# power-supplies-hw.net
KiCad netlist of a schematic drawn in Altium Designer
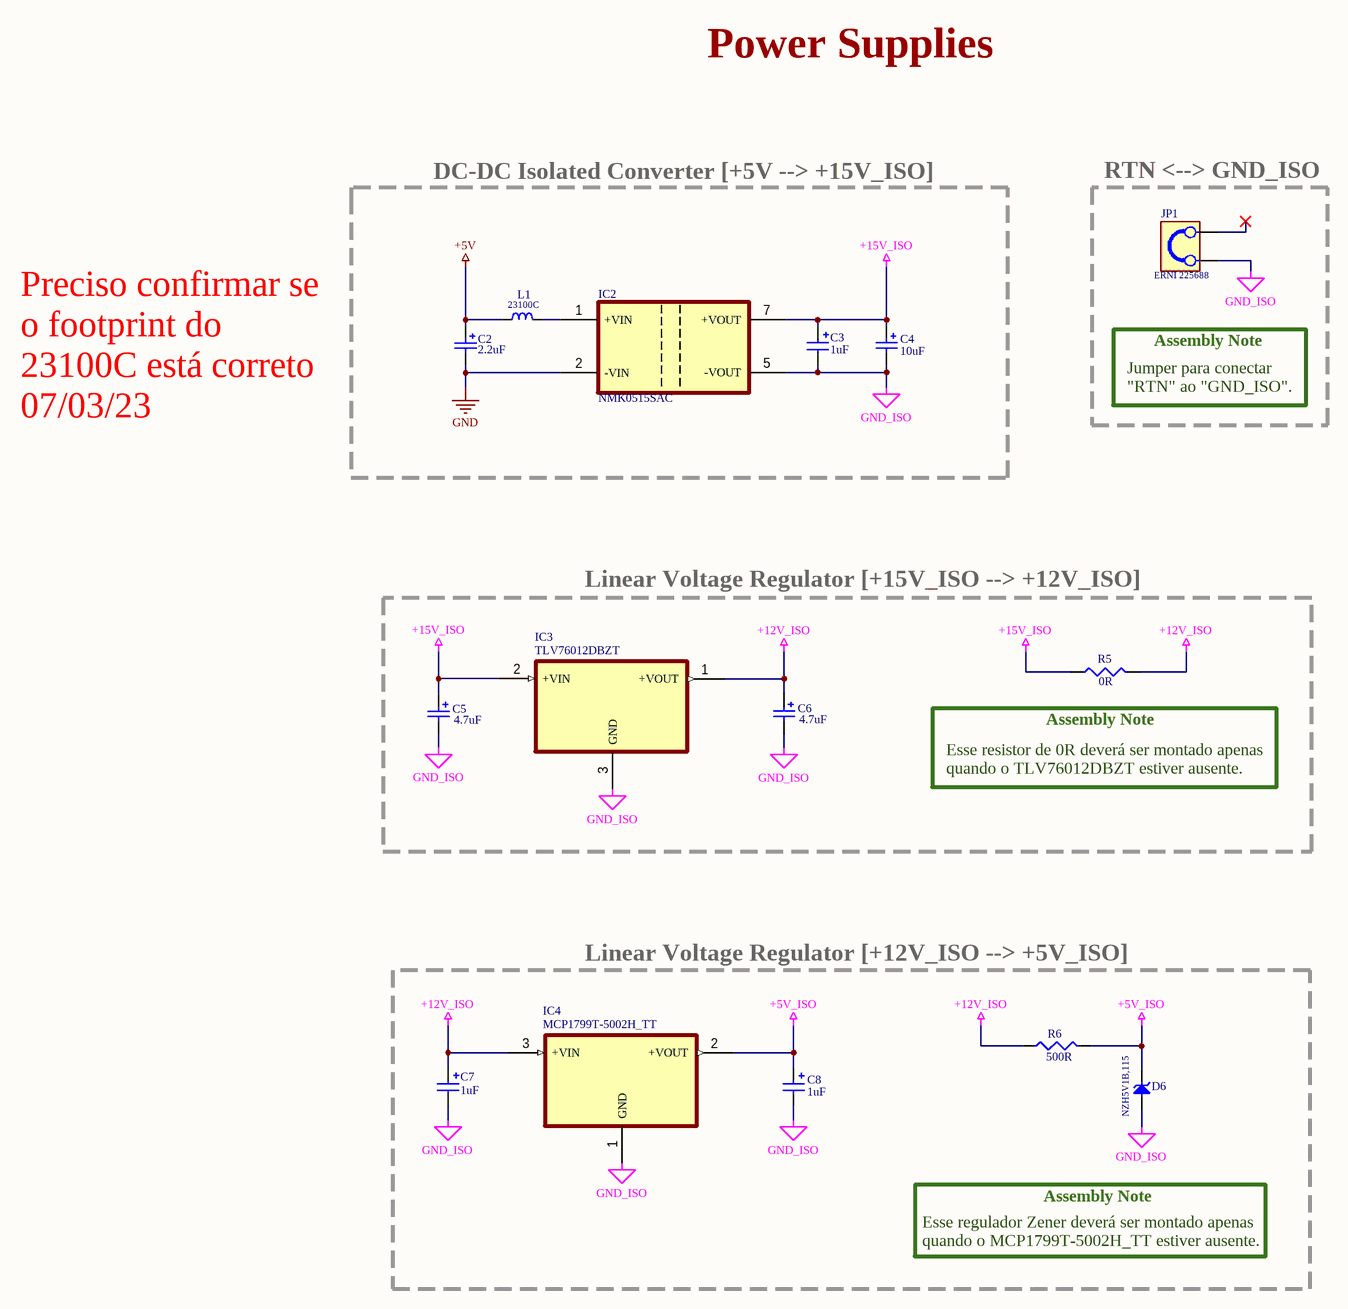
[diagram p0: power-supplies-hw.SchDoc]

(export (version "E")
  (design (tool "Eeschema 10.0.6"))
  (components
    (comp (ref "C2")
      (value "2.2uF")
      (footprint "C1206")
      (libsource (lib "acopians-powerspy-monitoring-hw-library-schematic") (part "Capacitor 2.2uF"))
    )
    (comp (ref "C3")
      (value "1uF")
      (footprint "C1206")
      (libsource (lib "acopians-powerspy-monitoring-hw-library-schematic") (part "Capacitor 1uF"))
    )
    (comp (ref "C4")
      (value "10uF")
      (footprint "C1206")
      (libsource (lib "acopians-powerspy-monitoring-hw-library-schematic") (part "Capacitor 10uF"))
    )
    (comp (ref "C5")
      (value "4.7uF")
      (footprint "C1206")
      (libsource (lib "acopians-powerspy-monitoring-hw-library-schematic") (part "Capacitor 4.7uF"))
    )
    (comp (ref "C6")
      (value "4.7uF")
      (footprint "C1206")
      (libsource (lib "acopians-powerspy-monitoring-hw-library-schematic") (part "Capacitor 4.7uF"))
    )
    (comp (ref "C7")
      (value "1uF")
      (footprint "C1206")
      (libsource (lib "acopians-powerspy-monitoring-hw-library-schematic") (part "Capacitor 1uF"))
    )
    (comp (ref "C8")
      (value "1uF")
      (footprint "C1206")
      (libsource (lib "acopians-powerspy-monitoring-hw-library-schematic") (part "Capacitor 1uF"))
    )
    (comp (ref "D6")
      (value "NZH5V1B,115")
      (footprint "SOD-123F-2")
      (description "5.1V, SOD-123F-2")
      (libsource (lib "acopians-powerspy-monitoring-hw-library-schematic") (part "Zener NZH5V1B,115"))
    )
    (comp (ref "IC2")
      (value "NMK0515SAC")
      (footprint "NMK0515SAC")
      (description "3kVDC Isolated 2W Single Output DC-DC Converter")
      (libsource (lib "acopians-powerspy-monitoring-hw-library-schematic") (part "NMK0515SAC"))
    )
    (comp (ref "IC3")
      (value "TLV76012DBZT")
      (footprint "SOT_23_3")
      (description "Linear-Voltage Regulator, +12V Fixed-Output, 100mA")
      (libsource (lib "acopians-powerspy-monitoring-hw-library-schematic") (part "TLV76012DBZT"))
    )
    (comp (ref "IC4")
      (value "MCP1799T-5002H_TT")
      (footprint "SOT_23_3")
      (description "High-Voltage Automotive LDO, 80mA")
      (libsource (lib "acopians-powerspy-monitoring-hw-library-schematic") (part "MCP1799T-5002H_TT"))
    )
    (comp (ref "JP1")
      (value "ERNI 225688")
      (footprint "ERNI 225688")
      (libsource (lib "acopians-powerspy-monitoring-hw-library-schematic") (part "ERNI 225688"))
    )
    (comp (ref "L1")
      (value "23100C")
      (footprint "23100C")
      (description "Bobbin Wound Surface Mount Inductors, 10uH, 138mOhms, Imax 1.02A")
      (libsource (lib "acopians-powerspy-monitoring-hw-library-schematic") (part "23100C"))
    )
    (comp (ref "R5")
      (value "0R")
      (footprint "R1210")
      (description "Size 1210")
      (libsource (lib "acopians-powerspy-monitoring-hw-library-schematic") (part "Resistor 0R"))
    )
    (comp (ref "R6")
      (value "500R")
      (footprint "Resistor 0805")
      (libsource (lib "acopians-powerspy-monitoring-hw-library-schematic") (part "Resistor 500R"))
    )
  )
  (nets
    (net (code "1") (name "+5V") (class "Default")
      (node (ref "C2") (pin "1") (pinfunction "1_1") (pintype "passive"))
      (node (ref "L1") (pin "1") (pinfunction "1_1") (pintype "passive"))
    )
    (net (code "2") (name "+5V_ISO") (class "Default")
      (node (ref "C8") (pin "1") (pinfunction "1_1") (pintype "passive"))
      (node (ref "D6") (pin "1") (pintype "passive"))
      (node (ref "IC4") (pin "2") (pinfunction "+VOUT_2") (pintype "output"))
      (node (ref "R6") (pin "2") (pinfunction "2_2") (pintype "passive"))
    )
    (net (code "3") (name "+12V_ISO") (class "Default")
      (node (ref "C6") (pin "1") (pinfunction "1_1") (pintype "passive"))
      (node (ref "C7") (pin "1") (pinfunction "1_1") (pintype "passive"))
      (node (ref "IC3") (pin "1") (pinfunction "+VOUT_1") (pintype "output"))
      (node (ref "IC4") (pin "3") (pinfunction "+VIN_3") (pintype "input"))
      (node (ref "R5") (pin "2") (pinfunction "2_2") (pintype "passive"))
      (node (ref "R6") (pin "1") (pinfunction "1_1") (pintype "passive"))
    )
    (net (code "4") (name "+15V_ISO") (class "Default")
      (node (ref "C3") (pin "1") (pinfunction "1_1") (pintype "passive"))
      (node (ref "C4") (pin "1") (pinfunction "1_1") (pintype "passive"))
      (node (ref "C5") (pin "1") (pinfunction "1_1") (pintype "passive"))
      (node (ref "IC2") (pin "7") (pinfunction "+VOUT_7") (pintype "passive"))
      (node (ref "IC3") (pin "2") (pinfunction "+VIN_2") (pintype "input"))
      (node (ref "R5") (pin "1") (pinfunction "1_1") (pintype "passive"))
    )
    (net (code "5") (name "GND") (class "Default")
      (node (ref "C2") (pin "2") (pinfunction "2_2") (pintype "passive"))
      (node (ref "IC2") (pin "2") (pinfunction "-VIN_2") (pintype "passive"))
    )
    (net (code "6") (name "GND_ISO") (class "Default")
      (node (ref "C3") (pin "2") (pinfunction "2_2") (pintype "passive"))
      (node (ref "C4") (pin "2") (pinfunction "2_2") (pintype "passive"))
      (node (ref "C5") (pin "2") (pinfunction "2_2") (pintype "passive"))
      (node (ref "C6") (pin "2") (pinfunction "2_2") (pintype "passive"))
      (node (ref "C7") (pin "2") (pinfunction "2_2") (pintype "passive"))
      (node (ref "C8") (pin "2") (pinfunction "2_2") (pintype "passive"))
      (node (ref "D6") (pin "2") (pintype "passive"))
      (node (ref "IC2") (pin "5") (pinfunction "-VOUT_5") (pintype "passive"))
      (node (ref "IC3") (pin "3") (pinfunction "GND_3") (pintype "passive"))
      (node (ref "IC4") (pin "1") (pinfunction "GND_1") (pintype "passive"))
      (node (ref "JP1") (pin "1") (pinfunction "1_1") (pintype "passive"))
    )
    (net (code "7") (name "Net-(IC2-+VIN)") (class "Default")
      (node (ref "IC2") (pin "1") (pinfunction "+VIN_1") (pintype "passive"))
      (node (ref "L1") (pin "2") (pinfunction "2_2") (pintype "passive"))
    )
    (net (code "8") (name "unconnected-(JP1-Pad2)") (class "Default")
      (node (ref "JP1") (pin "2") (pinfunction "2_2") (pintype "passive+no_connect"))
    )
  )
)
